# CAN.net
KiCad netlist of a schematic drawn in Altium Designer
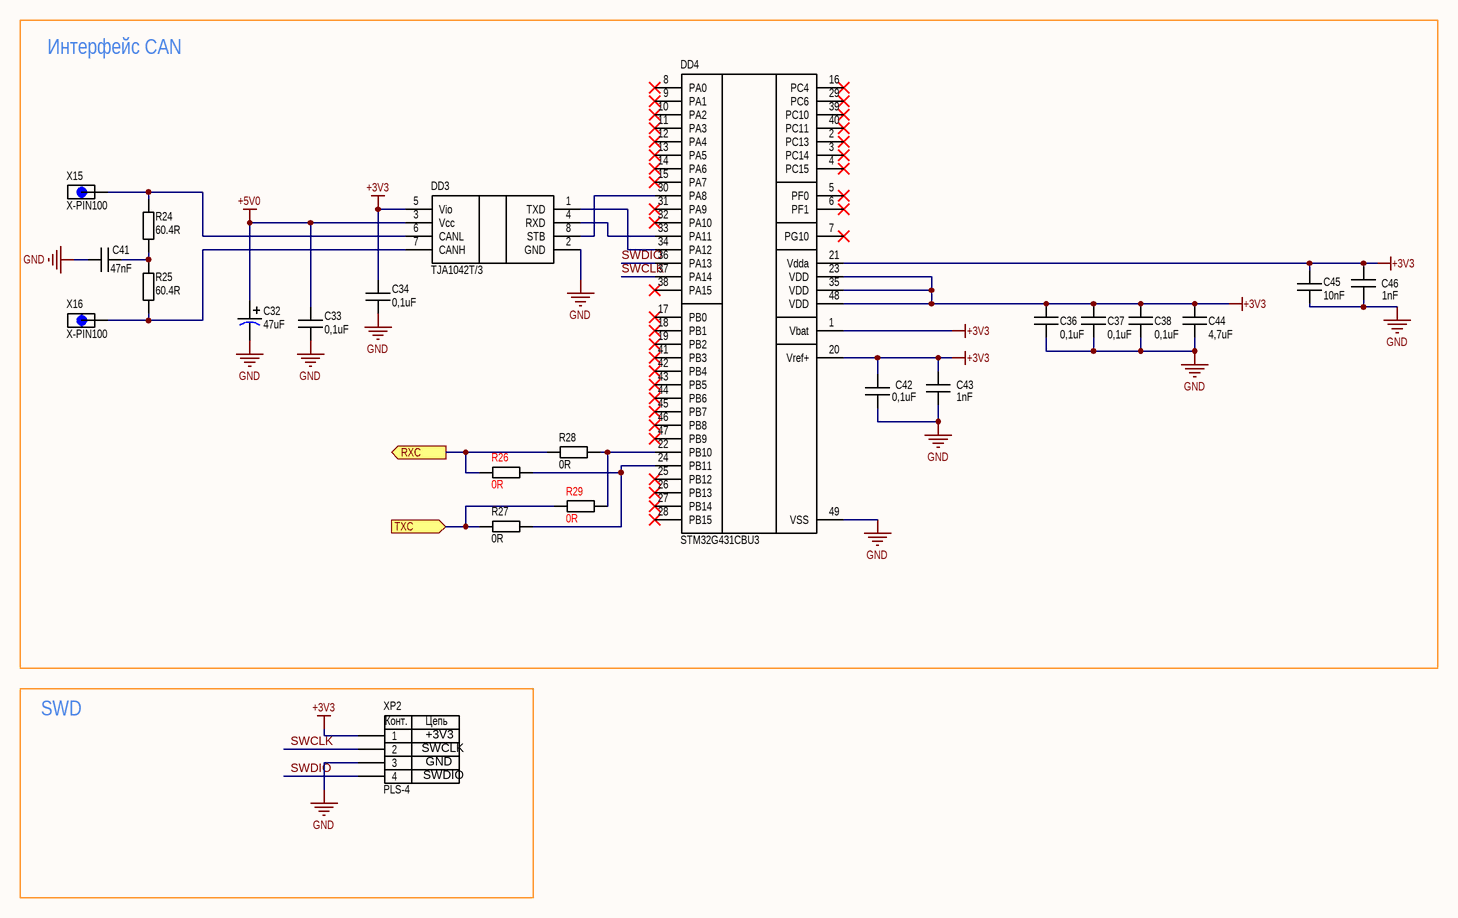
[diagram p0: CAN.SchDoc]

(export (version "E")
  (design (tool "Eeschema 10.0.6"))
  (components
    (comp (ref "C32")
      (value "47uF")
      (footprint "B1411_3528")
      (description "CP1411B 47UF 6V3")
      (fields
        (field (name "PART NUMBER") "SMD CAP TANTAL 47uF ±10% 6V3 1411B")
        (field (name "ADDED_BY") "ridel_av@teslatec.ru")
      )
      (libsource (lib "81801_1") (part "CP1411B-47UF"))
    )
    (comp (ref "C33")
      (value "0,1uF")
      (footprint "0805C")
      (description "C0805 0,1uF")
      (fields
        (field (name "PART NUMBER") "SMD CAP CER 0.1uF ±10% 25V X7R 0805")
        (field (name "ADDED_BY") "ridel_av@teslatec.ru")
      )
      (libsource (lib "81801_1") (part "C0805-0,1uF"))
    )
    (comp (ref "C34")
      (value "0,1uF")
      (footprint "0805C")
      (description "C0805 0,1uF")
      (fields
        (field (name "PART NUMBER") "SMD CAP CER 0.1uF ±10% 25V X7R 0805")
        (field (name "ADDED_BY") "ridel_av@teslatec.ru")
      )
      (libsource (lib "81801_1") (part "C0805-0,1uF"))
    )
    (comp (ref "C36")
      (value "0,1uF")
      (footprint "0805C")
      (description "C0805 0,1uF")
      (fields
        (field (name "PART NUMBER") "SMD CAP CER 0.1uF ±10% 25V X7R 0805")
        (field (name "ADDED_BY") "ridel_av@teslatec.ru")
      )
      (libsource (lib "81801_1") (part "C0805-0,1uF"))
    )
    (comp (ref "C37")
      (value "0,1uF")
      (footprint "0805C")
      (description "C0805 0,1uF")
      (fields
        (field (name "PART NUMBER") "SMD CAP CER 0.1uF ±10% 25V X7R 0805")
        (field (name "ADDED_BY") "ridel_av@teslatec.ru")
      )
      (libsource (lib "81801_1") (part "C0805-0,1uF"))
    )
    (comp (ref "C38")
      (value "0,1uF")
      (footprint "0805C")
      (description "C0805 0,1uF")
      (fields
        (field (name "PART NUMBER") "SMD CAP CER 0.1uF ±10% 25V X7R 0805")
        (field (name "ADDED_BY") "ridel_av@teslatec.ru")
      )
      (libsource (lib "81801_1") (part "C0805-0,1uF"))
    )
    (comp (ref "C41")
      (value "47nF")
      (footprint "0805C")
      (description "C0805 47nF 50V")
      (fields
        (field (name "PART NUMBER") "SMD CAP CER 47nF ±10% 25V C0G 0805")
        (field (name "ADDED_BY") "ridel_av@teslatec.ru")
      )
      (libsource (lib "81801_1") (part "C0805-47nF"))
    )
    (comp (ref "C42")
      (value "0,1uF")
      (footprint "0805C")
      (description "C0805 0,1uF")
      (fields
        (field (name "PART NUMBER") "SMD CAP CER 0.1uF ±10% 25V X7R 0805")
        (field (name "ADDED_BY") "ridel_av@teslatec.ru")
      )
      (libsource (lib "81801_1") (part "C0805-0,1uF"))
    )
    (comp (ref "C43")
      (value "1nF")
      (footprint "0805C")
      (description "C0805 1nF")
      (fields
        (field (name "PART NUMBER") "SMD CAP CER 1nF ±10% 50V X7R 0805")
        (field (name "ADDED_BY") "ridel_av@teslatec.ru")
      )
      (libsource (lib "81801_1") (part "C0805-1nF"))
    )
    (comp (ref "C44")
      (value "4,7uF")
      (footprint "0805C")
      (description "C0805 4,7uF 50V")
      (fields
        (field (name "PART NUMBER") "SMD CAP CER 4.7uF ±10% 50V X7R 0805")
        (field (name "ADDED_BY") "ridel_av@teslatec.ru")
      )
      (libsource (lib "81801_1") (part "C0805-4,7uF"))
    )
    (comp (ref "C45")
      (value "10nF")
      (footprint "0805C")
      (description "C0805 10nF")
      (fields
        (field (name "PART NUMBER") "SMD CAP CER 10nF ±10% 50V X7R 0805")
        (field (name "ADDED_BY") "ridel_av@teslatec.ru")
      )
      (libsource (lib "81801_1") (part "C0805-10nF"))
    )
    (comp (ref "C46")
      (value "1nF")
      (footprint "0805C")
      (description "C0805 1nF")
      (fields
        (field (name "PART NUMBER") "SMD CAP CER 1nF ±10% 50V X7R 0805")
        (field (name "ADDED_BY") "ridel_av@teslatec.ru")
      )
      (libsource (lib "81801_1") (part "C0805-1nF"))
    )
    (comp (ref "DD3")
      (value "TJA1042T/3")
      (footprint "SOIC-8")
      (description "High-speed CAN transceiver with Standby mode")
      (fields (field (name "ADDED_BY") "dolgopolova_ia@teslatec.ru"))
      (libsource (lib "81801_1") (part "TJA1042T/3"))
    )
    (comp (ref "DD4")
      (value "STM32G431CBU3")
      (footprint "TQFP-64")
      (description "Arm Cortex-M4 32b MCU+FPU, 170 MHz / 213 DMIPS, 128 KB Flash")
      (fields (field (name "ADDED_BY") "ridel_av@teslatec.ru"))
      (libsource (lib "81801_1") (part "STM32G431CBU3"))
    )
    (comp (ref "R24")
      (value "60.4R")
      (footprint "R0805")
      (description "R0805 SMD 60.4R OHM 1% ±100ppm/°C")
      (fields
        (field (name "PART NUMBER") "SMD RES 60.4 OHM 1% ±100ppm/°C 0805")
        (field (name "ADDED_BY") "ridel_av@teslatec.ru")
      )
      (libsource (lib "81801_1") (part "R0805-60.4R"))
    )
    (comp (ref "R25")
      (value "60.4R")
      (footprint "R0805")
      (description "R0805 SMD 60.4R OHM 1% ±100ppm/°C")
      (fields
        (field (name "PART NUMBER") "SMD RES 60.4 OHM 1% ±100ppm/°C 0805")
        (field (name "ADDED_BY") "ridel_av@teslatec.ru")
      )
      (libsource (lib "81801_1") (part "R0805-60.4R"))
    )
    (comp (ref "R26")
      (value "0R")
      (footprint "R1206")
      (description "R1206-0R")
      (fields
        (field (name "PART NUMBER") "SMD RES 0 OHM 1% ±100ppm/°C 1206")
        (field (name "ADDED_BY") "ridel_av@teslatec.ru")
      )
      (libsource (lib "81801_1") (part "R1206-0R"))
    )
    (comp (ref "R27")
      (value "0R")
      (footprint "R1206")
      (description "R1206-0R")
      (fields
        (field (name "PART NUMBER") "SMD RES 0 OHM 1% ±100ppm/°C 1206")
        (field (name "ADDED_BY") "ridel_av@teslatec.ru")
      )
      (libsource (lib "81801_1") (part "R1206-0R"))
    )
    (comp (ref "R28")
      (value "0R")
      (footprint "R1206")
      (description "R1206-0R")
      (fields
        (field (name "PART NUMBER") "SMD RES 0 OHM 1% ±100ppm/°C 1206")
        (field (name "ADDED_BY") "ridel_av@teslatec.ru")
      )
      (libsource (lib "81801_1") (part "R1206-0R"))
    )
    (comp (ref "R29")
      (value "0R")
      (footprint "R1206")
      (description "R1206-0R")
      (fields
        (field (name "PART NUMBER") "SMD RES 0 OHM 1% ±100ppm/°C 1206")
        (field (name "ADDED_BY") "ridel_av@teslatec.ru")
      )
      (libsource (lib "81801_1") (part "R1206-0R"))
    )
    (comp (ref "X15")
      (value "X-PIN100")
      (footprint "Xpin100")
      (fields (field (name "ADDED_BY") "ridel_av@teslatec.ru"))
      (libsource (lib "81801_1") (part "X-PIN100"))
    )
    (comp (ref "X16")
      (value "X-PIN100")
      (footprint "Xpin100")
      (fields (field (name "ADDED_BY") "ridel_av@teslatec.ru"))
      (libsource (lib "81801_1") (part "X-PIN100"))
    )
    (comp (ref "XP2")
      (value "PLS-4")
      (footprint "PLS-4")
      (description "HEADER 2.54mm")
      (fields (field (name "MATING PART") "BLS-4") (field (name "ADDED_BY") "irdolgopolowa@yandex.ru"))
      (libsource (lib "81801_1") (part "PLS-4"))
    )
  )
  (nets
    (net (code "1") (name "+3V3") (class "Default")
      (node (ref "C34") (pin "1") (pinfunction "1_1") (pintype "passive"))
      (node (ref "C36") (pin "1") (pinfunction "1_1") (pintype "passive"))
      (node (ref "C37") (pin "1") (pinfunction "1_1") (pintype "passive"))
      (node (ref "C38") (pin "1") (pinfunction "1_1") (pintype "passive"))
      (node (ref "C42") (pin "1") (pinfunction "1_1") (pintype "passive"))
      (node (ref "C43") (pin "1") (pinfunction "1_1") (pintype "passive"))
      (node (ref "C44") (pin "1") (pinfunction "1_1") (pintype "passive"))
      (node (ref "C45") (pin "1") (pinfunction "1_1") (pintype "passive"))
      (node (ref "C46") (pin "1") (pinfunction "1_1") (pintype "passive"))
      (node (ref "DD3") (pin "5") (pinfunction "Vio_5") (pintype "passive"))
      (node (ref "DD4") (pin "1") (pinfunction "Vbat_1") (pintype "passive"))
      (node (ref "DD4") (pin "20") (pinfunction "Vref+_20") (pintype "passive"))
      (node (ref "DD4") (pin "21") (pinfunction "Vdda_21") (pintype "passive"))
      (node (ref "DD4") (pin "23") (pinfunction "VDD_23") (pintype "passive"))
      (node (ref "DD4") (pin "35") (pinfunction "VDD_35") (pintype "passive"))
      (node (ref "DD4") (pin "48") (pinfunction "VDD_48") (pintype "passive"))
      (node (ref "XP2") (pin "1") (pinfunction "1_1") (pintype "passive"))
    )
    (net (code "2") (name "+5V0") (class "Default")
      (node (ref "C32") (pin "1") (pinfunction "1_1") (pintype "passive"))
      (node (ref "C33") (pin "1") (pinfunction "1_1") (pintype "passive"))
      (node (ref "DD3") (pin "3") (pinfunction "Vcc_3") (pintype "passive"))
    )
    (net (code "3") (name "/RXC") (class "Default")
      (node (ref "R26") (pin "2") (pinfunction "2_2") (pintype "passive"))
      (node (ref "R28") (pin "2") (pinfunction "2_2") (pintype "passive"))
    )
    (net (code "4") (name "/SWCLK") (class "Default")
      (node (ref "DD4") (pin "37") (pinfunction "PA14_37") (pintype "passive"))
      (node (ref "XP2") (pin "2") (pinfunction "2_2") (pintype "passive"))
    )
    (net (code "5") (name "/SWDIO") (class "Default")
      (node (ref "DD4") (pin "36") (pinfunction "PA13_36") (pintype "passive"))
      (node (ref "XP2") (pin "4") (pinfunction "4_4") (pintype "passive"))
    )
    (net (code "6") (name "/TXC") (class "Default")
      (node (ref "R27") (pin "2") (pinfunction "2_2") (pintype "passive"))
      (node (ref "R29") (pin "2") (pinfunction "2_2") (pintype "passive"))
    )
    (net (code "7") (name "GND") (class "Default")
      (node (ref "C32") (pin "2") (pinfunction "2_2") (pintype "passive"))
      (node (ref "C33") (pin "2") (pinfunction "2_2") (pintype "passive"))
      (node (ref "C34") (pin "2") (pinfunction "2_2") (pintype "passive"))
      (node (ref "C36") (pin "2") (pinfunction "2_2") (pintype "passive"))
      (node (ref "C37") (pin "2") (pinfunction "2_2") (pintype "passive"))
      (node (ref "C38") (pin "2") (pinfunction "2_2") (pintype "passive"))
      (node (ref "C41") (pin "1") (pinfunction "1_1") (pintype "passive"))
      (node (ref "C42") (pin "2") (pinfunction "2_2") (pintype "passive"))
      (node (ref "C43") (pin "2") (pinfunction "2_2") (pintype "passive"))
      (node (ref "C44") (pin "2") (pinfunction "2_2") (pintype "passive"))
      (node (ref "C45") (pin "2") (pinfunction "2_2") (pintype "passive"))
      (node (ref "C46") (pin "2") (pinfunction "2_2") (pintype "passive"))
      (node (ref "DD3") (pin "2") (pinfunction "GND_2") (pintype "passive"))
      (node (ref "DD4") (pin "49") (pinfunction "VSS_49") (pintype "passive"))
      (node (ref "XP2") (pin "3") (pinfunction "3_3") (pintype "passive"))
    )
    (net (code "8") (name "Net-(C41-Pad2)") (class "Default")
      (node (ref "C41") (pin "2") (pinfunction "2_2") (pintype "passive"))
      (node (ref "R24") (pin "1") (pinfunction "1_1") (pintype "passive"))
      (node (ref "R25") (pin "2") (pinfunction "2_2") (pintype "passive"))
    )
    (net (code "9") (name "Net-(DD3-CANH)") (class "Default")
      (node (ref "DD3") (pin "7") (pinfunction "CANH_7") (pintype "passive"))
      (node (ref "R25") (pin "1") (pinfunction "1_1") (pintype "passive"))
      (node (ref "X16") (pin "1") (pintype "passive"))
    )
    (net (code "10") (name "Net-(DD3-CANL)") (class "Default")
      (node (ref "DD3") (pin "6") (pinfunction "CANL_6") (pintype "passive"))
      (node (ref "R24") (pin "2") (pinfunction "2_2") (pintype "passive"))
      (node (ref "X15") (pin "1") (pintype "passive"))
    )
    (net (code "11") (name "Net-(DD3-RXD)") (class "Default")
      (node (ref "DD3") (pin "4") (pinfunction "RXD_4") (pintype "passive"))
      (node (ref "DD4") (pin "33") (pinfunction "PA11_33") (pintype "passive"))
    )
    (net (code "12") (name "Net-(DD3-STB)") (class "Default")
      (node (ref "DD3") (pin "8") (pinfunction "STB_8") (pintype "passive"))
      (node (ref "DD4") (pin "30") (pinfunction "PA8_30") (pintype "passive"))
    )
    (net (code "13") (name "Net-(DD3-TXD)") (class "Default")
      (node (ref "DD3") (pin "1") (pinfunction "TXD_1") (pintype "passive"))
      (node (ref "DD4") (pin "34") (pinfunction "PA12_34") (pintype "passive"))
    )
    (net (code "14") (name "Net-(DD4-PB10)") (class "Default")
      (node (ref "DD4") (pin "22") (pinfunction "PB10_22") (pintype "passive"))
      (node (ref "R28") (pin "1") (pinfunction "1_1") (pintype "passive"))
      (node (ref "R29") (pin "1") (pinfunction "1_1") (pintype "passive"))
    )
    (net (code "15") (name "Net-(DD4-PB11)") (class "Default")
      (node (ref "DD4") (pin "24") (pinfunction "PB11_24") (pintype "passive"))
      (node (ref "R26") (pin "1") (pinfunction "1_1") (pintype "passive"))
      (node (ref "R27") (pin "1") (pinfunction "1_1") (pintype "passive"))
    )
    (net (code "16") (name "unconnected-(DD4-PA0-Pad8)") (class "Default")
      (node (ref "DD4") (pin "8") (pinfunction "PA0_8") (pintype "passive+no_connect"))
    )
    (net (code "17") (name "unconnected-(DD4-PA1-Pad9)") (class "Default")
      (node (ref "DD4") (pin "9") (pinfunction "PA1_9") (pintype "passive+no_connect"))
    )
    (net (code "18") (name "unconnected-(DD4-PA2-Pad10)") (class "Default")
      (node (ref "DD4") (pin "10") (pinfunction "PA2_10") (pintype "passive+no_connect"))
    )
    (net (code "19") (name "unconnected-(DD4-PA3-Pad11)") (class "Default")
      (node (ref "DD4") (pin "11") (pinfunction "PA3_11") (pintype "passive+no_connect"))
    )
    (net (code "20") (name "unconnected-(DD4-PA4-Pad12)") (class "Default")
      (node (ref "DD4") (pin "12") (pinfunction "PA4_12") (pintype "passive+no_connect"))
    )
    (net (code "21") (name "unconnected-(DD4-PA5-Pad13)") (class "Default")
      (node (ref "DD4") (pin "13") (pinfunction "PA5_13") (pintype "passive+no_connect"))
    )
    (net (code "22") (name "unconnected-(DD4-PA6-Pad14)") (class "Default")
      (node (ref "DD4") (pin "14") (pinfunction "PA6_14") (pintype "passive+no_connect"))
    )
    (net (code "23") (name "unconnected-(DD4-PA7-Pad15)") (class "Default")
      (node (ref "DD4") (pin "15") (pinfunction "PA7_15") (pintype "passive+no_connect"))
    )
    (net (code "24") (name "unconnected-(DD4-PA9-Pad31)") (class "Default")
      (node (ref "DD4") (pin "31") (pinfunction "PA9_31") (pintype "passive+no_connect"))
    )
    (net (code "25") (name "unconnected-(DD4-PA10-Pad32)") (class "Default")
      (node (ref "DD4") (pin "32") (pinfunction "PA10_32") (pintype "passive+no_connect"))
    )
    (net (code "26") (name "unconnected-(DD4-PA15-Pad38)") (class "Default")
      (node (ref "DD4") (pin "38") (pinfunction "PA15_38") (pintype "passive+no_connect"))
    )
    (net (code "27") (name "unconnected-(DD4-PB0-Pad17)") (class "Default")
      (node (ref "DD4") (pin "17") (pinfunction "PB0_17") (pintype "passive+no_connect"))
    )
    (net (code "28") (name "unconnected-(DD4-PB1-Pad18)") (class "Default")
      (node (ref "DD4") (pin "18") (pinfunction "PB1_18") (pintype "passive+no_connect"))
    )
    (net (code "29") (name "unconnected-(DD4-PB2-Pad19)") (class "Default")
      (node (ref "DD4") (pin "19") (pinfunction "PB2_19") (pintype "passive+no_connect"))
    )
    (net (code "30") (name "unconnected-(DD4-PB3-Pad41)") (class "Default")
      (node (ref "DD4") (pin "41") (pinfunction "PB3_41") (pintype "passive+no_connect"))
    )
    (net (code "31") (name "unconnected-(DD4-PB4-Pad42)") (class "Default")
      (node (ref "DD4") (pin "42") (pinfunction "PB4_42") (pintype "passive+no_connect"))
    )
    (net (code "32") (name "unconnected-(DD4-PB5-Pad43)") (class "Default")
      (node (ref "DD4") (pin "43") (pinfunction "PB5_43") (pintype "passive+no_connect"))
    )
    (net (code "33") (name "unconnected-(DD4-PB6-Pad44)") (class "Default")
      (node (ref "DD4") (pin "44") (pinfunction "PB6_44") (pintype "passive+no_connect"))
    )
    (net (code "34") (name "unconnected-(DD4-PB7-Pad45)") (class "Default")
      (node (ref "DD4") (pin "45") (pinfunction "PB7_45") (pintype "passive+no_connect"))
    )
    (net (code "35") (name "unconnected-(DD4-PB8-Pad46)") (class "Default")
      (node (ref "DD4") (pin "46") (pinfunction "PB8_46") (pintype "passive+no_connect"))
    )
    (net (code "36") (name "unconnected-(DD4-PB9-Pad47)") (class "Default")
      (node (ref "DD4") (pin "47") (pinfunction "PB9_47") (pintype "passive+no_connect"))
    )
    (net (code "37") (name "unconnected-(DD4-PB12-Pad25)") (class "Default")
      (node (ref "DD4") (pin "25") (pinfunction "PB12_25") (pintype "passive+no_connect"))
    )
    (net (code "38") (name "unconnected-(DD4-PB13-Pad26)") (class "Default")
      (node (ref "DD4") (pin "26") (pinfunction "PB13_26") (pintype "passive+no_connect"))
    )
    (net (code "39") (name "unconnected-(DD4-PB14-Pad27)") (class "Default")
      (node (ref "DD4") (pin "27") (pinfunction "PB14_27") (pintype "passive+no_connect"))
    )
    (net (code "40") (name "unconnected-(DD4-PB15-Pad28)") (class "Default")
      (node (ref "DD4") (pin "28") (pinfunction "PB15_28") (pintype "passive+no_connect"))
    )
    (net (code "41") (name "unconnected-(DD4-PC4-Pad16)") (class "Default")
      (node (ref "DD4") (pin "16") (pinfunction "PC4_16") (pintype "passive+no_connect"))
    )
    (net (code "42") (name "unconnected-(DD4-PC6-Pad29)") (class "Default")
      (node (ref "DD4") (pin "29") (pinfunction "PC6_29") (pintype "passive+no_connect"))
    )
    (net (code "43") (name "unconnected-(DD4-PC10-Pad39)") (class "Default")
      (node (ref "DD4") (pin "39") (pinfunction "PC10_39") (pintype "passive+no_connect"))
    )
    (net (code "44") (name "unconnected-(DD4-PC11-Pad40)") (class "Default")
      (node (ref "DD4") (pin "40") (pinfunction "PC11_40") (pintype "passive+no_connect"))
    )
    (net (code "45") (name "unconnected-(DD4-PC13-Pad2)") (class "Default")
      (node (ref "DD4") (pin "2") (pinfunction "PC13_2") (pintype "passive+no_connect"))
    )
    (net (code "46") (name "unconnected-(DD4-PC14-Pad3)") (class "Default")
      (node (ref "DD4") (pin "3") (pinfunction "PC14_3") (pintype "passive+no_connect"))
    )
    (net (code "47") (name "unconnected-(DD4-PC15-Pad4)") (class "Default")
      (node (ref "DD4") (pin "4") (pinfunction "PC15_4") (pintype "passive+no_connect"))
    )
    (net (code "48") (name "unconnected-(DD4-PF0-Pad5)") (class "Default")
      (node (ref "DD4") (pin "5") (pinfunction "PF0_5") (pintype "passive+no_connect"))
    )
    (net (code "49") (name "unconnected-(DD4-PF1-Pad6)") (class "Default")
      (node (ref "DD4") (pin "6") (pinfunction "PF1_6") (pintype "passive+no_connect"))
    )
    (net (code "50") (name "unconnected-(DD4-PG10-Pad7)") (class "Default")
      (node (ref "DD4") (pin "7") (pinfunction "PG10_7") (pintype "passive+no_connect"))
    )
  )
)
